# sensor_28mm.net
KiCad netlist of a schematic drawn in EAGLE
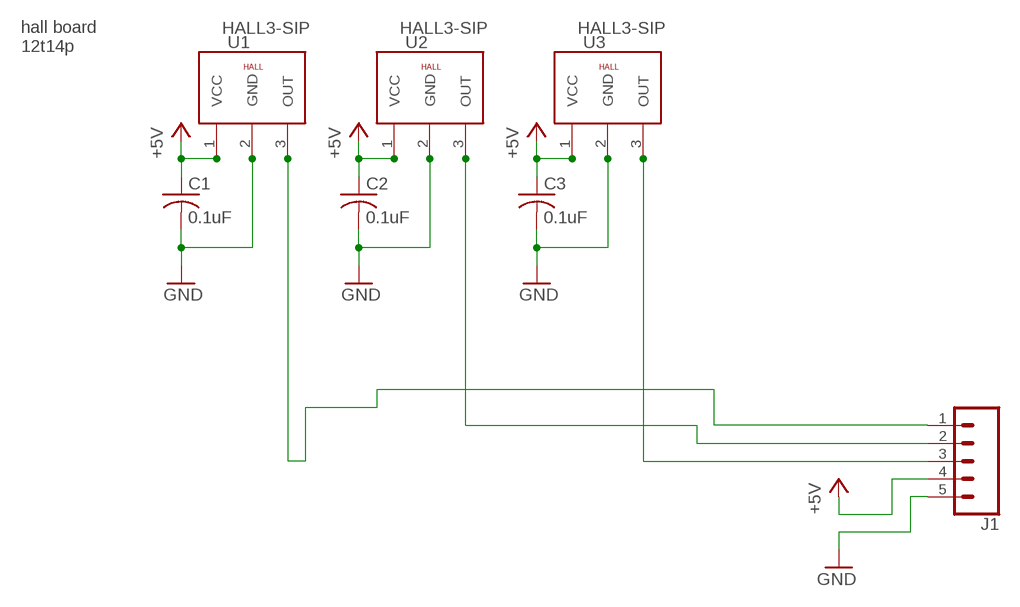
[diagram p0: schematic, sheet 1]

(export (version "E")
  (design (tool "Eeschema 10.0.6"))
  (components
    (comp (ref "C1")
      (value "0.1uF")
      (footprint "eagle-import:C0603")
      (libsource (lib "eagle-import") (part "C-USC0603"))
    )
    (comp (ref "C2")
      (value "0.1uF")
      (footprint "eagle-import:C0603")
      (libsource (lib "eagle-import") (part "C-USC0603"))
    )
    (comp (ref "C3")
      (value "0.1uF")
      (footprint "eagle-import:C0603")
      (libsource (lib "eagle-import") (part "C-USC0603"))
    )
    (comp (ref "J1")
      (value "CONN_05PTH_LONGPADS")
      (footprint "eagle-import:1X05_LONGPADS")
      (libsource (lib "eagle-import") (part "CONN_05PTH_LONGPADS"))
    )
    (comp (ref "U1")
      (value "HALL3-SIP")
      (footprint "eagle-import:3PINS1,27")
      (libsource (lib "eagle-import") (part "HALL3-SIP"))
    )
    (comp (ref "U2")
      (value "HALL3-SIP")
      (footprint "eagle-import:3PINS1,27")
      (libsource (lib "eagle-import") (part "HALL3-SIP"))
    )
    (comp (ref "U3")
      (value "HALL3-SIP")
      (footprint "eagle-import:3PINS1,27")
      (libsource (lib "eagle-import") (part "HALL3-SIP"))
    )
  )
  (nets
    (net (code "1") (name "+5V") (class "Default")
      (node (ref "C1") (pin "1") (pinfunction "1_1") (pintype "passive"))
      (node (ref "C2") (pin "1") (pinfunction "1_1") (pintype "passive"))
      (node (ref "C3") (pin "1") (pinfunction "1_1") (pintype "passive"))
      (node (ref "J1") (pin "4") (pinfunction "4_4") (pintype "passive"))
      (node (ref "U1") (pin "1") (pinfunction "VCC_1") (pintype "bidirectional"))
      (node (ref "U2") (pin "1") (pinfunction "VCC_1") (pintype "bidirectional"))
      (node (ref "U3") (pin "1") (pinfunction "VCC_1") (pintype "bidirectional"))
    )
    (net (code "2") (name "GND") (class "Default")
      (node (ref "C1") (pin "2") (pinfunction "2_2") (pintype "passive"))
      (node (ref "C2") (pin "2") (pinfunction "2_2") (pintype "passive"))
      (node (ref "C3") (pin "2") (pinfunction "2_2") (pintype "passive"))
      (node (ref "J1") (pin "5") (pinfunction "5_5") (pintype "passive"))
      (node (ref "U1") (pin "2") (pinfunction "GND_2") (pintype "bidirectional"))
      (node (ref "U2") (pin "2") (pinfunction "GND_2") (pintype "bidirectional"))
      (node (ref "U3") (pin "2") (pinfunction "GND_2") (pintype "bidirectional"))
    )
    (net (code "3") (name "Net-(U1-OUT)") (class "Default")
      (node (ref "J1") (pin "1") (pinfunction "1_1") (pintype "passive"))
      (node (ref "U1") (pin "3") (pinfunction "OUT_3") (pintype "bidirectional"))
    )
    (net (code "4") (name "Net-(U2-OUT)") (class "Default")
      (node (ref "J1") (pin "2") (pinfunction "2_2") (pintype "passive"))
      (node (ref "U2") (pin "3") (pinfunction "OUT_3") (pintype "bidirectional"))
    )
    (net (code "5") (name "Net-(U3-OUT)") (class "Default")
      (node (ref "J1") (pin "3") (pinfunction "3_3") (pintype "passive"))
      (node (ref "U3") (pin "3") (pinfunction "OUT_3") (pintype "bidirectional"))
    )
  )
)
